# design.net
KiCad netlist of a schematic drawn in Altium Designer
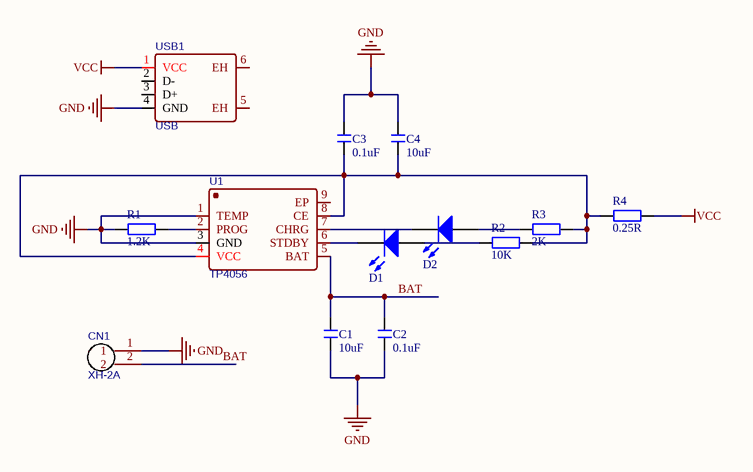
[diagram p0: 锂电池充电器原理图.SchDoc]

(export (version "E")
  (design (tool "Eeschema 10.0.6"))
  (components
    (comp (ref "C1")
      (value "10uF")
      (footprint "0805C")
      (description "贴片电容")
      (libsource (lib "原理图库") (part "C"))
    )
    (comp (ref "C2")
      (value "0.1uF")
      (footprint "0805C")
      (description "贴片电容")
      (libsource (lib "原理图库") (part "C"))
    )
    (comp (ref "C3")
      (value "0.1uF")
      (footprint "0805C")
      (description "贴片电容")
      (libsource (lib "原理图库") (part "C"))
    )
    (comp (ref "C4")
      (value "10uF")
      (footprint "0805C")
      (description "贴片电容")
      (libsource (lib "原理图库") (part "C"))
    )
    (comp (ref "CN1")
      (value "XH-2A")
      (footprint "XH-2P")
      (description "插接件")
      (fields (field (name "BOM_SUPPLIER PART") "C20079"))
      (libsource (lib "原理图库") (part "XH-2A"))
    )
    (comp (ref "D1")
      (value "LED")
      (footprint "LED 0805B")
      (description "发光二极管")
      (fields (field (name "PUBLISHER") "Altium Limited"))
      (libsource (lib "原理图库") (part "LED"))
    )
    (comp (ref "D2")
      (value "LED")
      (footprint "LED 0805B")
      (description "发光二极管")
      (fields (field (name "PUBLISHER") "Altium Limited"))
      (libsource (lib "原理图库") (part "LED"))
    )
    (comp (ref "R1")
      (value "1.2K")
      (footprint "0805R")
      (description "贴片电阻")
      (fields (field (name "版权归属") "来自淘宝 ID：黄晶宝石"))
      (libsource (lib "原理图库") (part "R"))
    )
    (comp (ref "R2")
      (value "10K")
      (footprint "0805R")
      (description "贴片电阻")
      (fields (field (name "版权归属") "来自淘宝 ID：黄晶宝石"))
      (libsource (lib "原理图库") (part "R"))
    )
    (comp (ref "R3")
      (value "2K")
      (footprint "0805R")
      (description "贴片电阻")
      (fields (field (name "版权归属") "来自淘宝 ID：黄晶宝石"))
      (libsource (lib "原理图库") (part "R"))
    )
    (comp (ref "R4")
      (value "0.25R")
      (footprint "0805R")
      (description "贴片电阻")
      (fields (field (name "版权归属") "来自淘宝 ID：黄晶宝石"))
      (libsource (lib "原理图库") (part "R"))
    )
    (comp (ref "U1")
      (value "TP4056")
      (footprint "ESOP8")
      (description "充电芯片 ESOP8")
      (fields (field (name "BOM_SUPPLIER PART") "C725790") (field (name "CONTRIBUTOR") "LCSC"))
      (libsource (lib "原理图库") (part "TP4056"))
    )
    (comp (ref "USB1")
      (value "USB")
      (footprint "USB_A 插头")
      (description "USB_Type-A 插头")
      (fields
        (field (name "BOM_MANUFACTURER PART") "USB-05")
        (field (name "BOM_SUPPLIER PART") "C112454")
        (field (name "CONTRIBUTOR") "LCSC")
      )
      (libsource (lib "原理图库") (part "USB"))
    )
  )
  (nets
    (net (code "1") (name "/BAT") (class "Default")
      (node (ref "C1") (pin "2") (pinfunction "2_2") (pintype "passive"))
      (node (ref "C2") (pin "2") (pinfunction "2_2") (pintype "passive"))
      (node (ref "CN1") (pin "2") (pinfunction "2_2") (pintype "passive"))
      (node (ref "U1") (pin "5") (pinfunction "BAT_5") (pintype "passive"))
    )
    (net (code "2") (name "GND") (class "Default")
      (node (ref "C1") (pin "1") (pinfunction "1_1") (pintype "passive"))
      (node (ref "C2") (pin "1") (pinfunction "1_1") (pintype "passive"))
      (node (ref "C3") (pin "1") (pinfunction "1_1") (pintype "passive"))
      (node (ref "C4") (pin "1") (pinfunction "1_1") (pintype "passive"))
      (node (ref "CN1") (pin "1") (pinfunction "1_1") (pintype "passive"))
      (node (ref "R1") (pin "1") (pinfunction "1_1") (pintype "passive"))
      (node (ref "U1") (pin "1") (pinfunction "TEMP_1") (pintype "passive"))
      (node (ref "U1") (pin "3") (pinfunction "GND_3") (pintype "passive"))
      (node (ref "USB1") (pin "4") (pinfunction "GND_4") (pintype "passive"))
    )
    (net (code "3") (name "Net-(D1-A)") (class "Default")
      (node (ref "D1") (pin "1") (pinfunction "A_1") (pintype "passive"))
      (node (ref "R2") (pin "1") (pinfunction "1_1") (pintype "passive"))
    )
    (net (code "4") (name "Net-(D1-K)") (class "Default")
      (node (ref "D1") (pin "2") (pinfunction "K_2") (pintype "passive"))
      (node (ref "U1") (pin "6") (pinfunction "STDBY_6") (pintype "passive"))
    )
    (net (code "5") (name "Net-(D2-A)") (class "Default")
      (node (ref "D2") (pin "1") (pinfunction "A_1") (pintype "passive"))
      (node (ref "R3") (pin "1") (pinfunction "1_1") (pintype "passive"))
    )
    (net (code "6") (name "Net-(D2-K)") (class "Default")
      (node (ref "D2") (pin "2") (pinfunction "K_2") (pintype "passive"))
      (node (ref "U1") (pin "7") (pinfunction "CHRG_7") (pintype "passive"))
    )
    (net (code "7") (name "Net-(U1-CE)") (class "Default")
      (node (ref "C3") (pin "2") (pinfunction "2_2") (pintype "passive"))
      (node (ref "C4") (pin "2") (pinfunction "2_2") (pintype "passive"))
      (node (ref "R2") (pin "2") (pinfunction "2_2") (pintype "passive"))
      (node (ref "R3") (pin "2") (pinfunction "2_2") (pintype "passive"))
      (node (ref "R4") (pin "1") (pinfunction "1_1") (pintype "passive"))
      (node (ref "U1") (pin "4") (pinfunction "VCC_4") (pintype "passive"))
      (node (ref "U1") (pin "8") (pinfunction "CE_8") (pintype "passive"))
    )
    (net (code "8") (name "Net-(U1-PROG)") (class "Default")
      (node (ref "R1") (pin "2") (pinfunction "2_2") (pintype "passive"))
      (node (ref "U1") (pin "2") (pinfunction "PROG_2") (pintype "passive"))
    )
    (net (code "9") (name "VCC") (class "Default")
      (node (ref "R4") (pin "2") (pinfunction "2_2") (pintype "passive"))
      (node (ref "USB1") (pin "1") (pinfunction "VCC_1") (pintype "passive"))
    )
    (net (code "10") (name "unconnected-(U1-EP-Pad9)") (class "Default")
      (node (ref "U1") (pin "9") (pinfunction "EP_9") (pintype "passive"))
    )
    (net (code "11") (name "unconnected-(USB1-D+-Pad3)") (class "Default")
      (node (ref "USB1") (pin "3") (pinfunction "D+_3") (pintype "passive"))
    )
    (net (code "12") (name "unconnected-(USB1-D--Pad2)") (class "Default")
      (node (ref "USB1") (pin "2") (pinfunction "D-_2") (pintype "passive"))
    )
    (net (code "13") (name "unconnected-(USB1-EH-Pad5)") (class "Default")
      (node (ref "USB1") (pin "5") (pinfunction "EH_5") (pintype "passive"))
    )
    (net (code "14") (name "unconnected-(USB1-EH-Pad6)") (class "Default")
      (node (ref "USB1") (pin "6") (pinfunction "EH_6") (pintype "passive"))
    )
  )
)
